# Power.net
KiCad netlist of a schematic drawn in Altium Designer
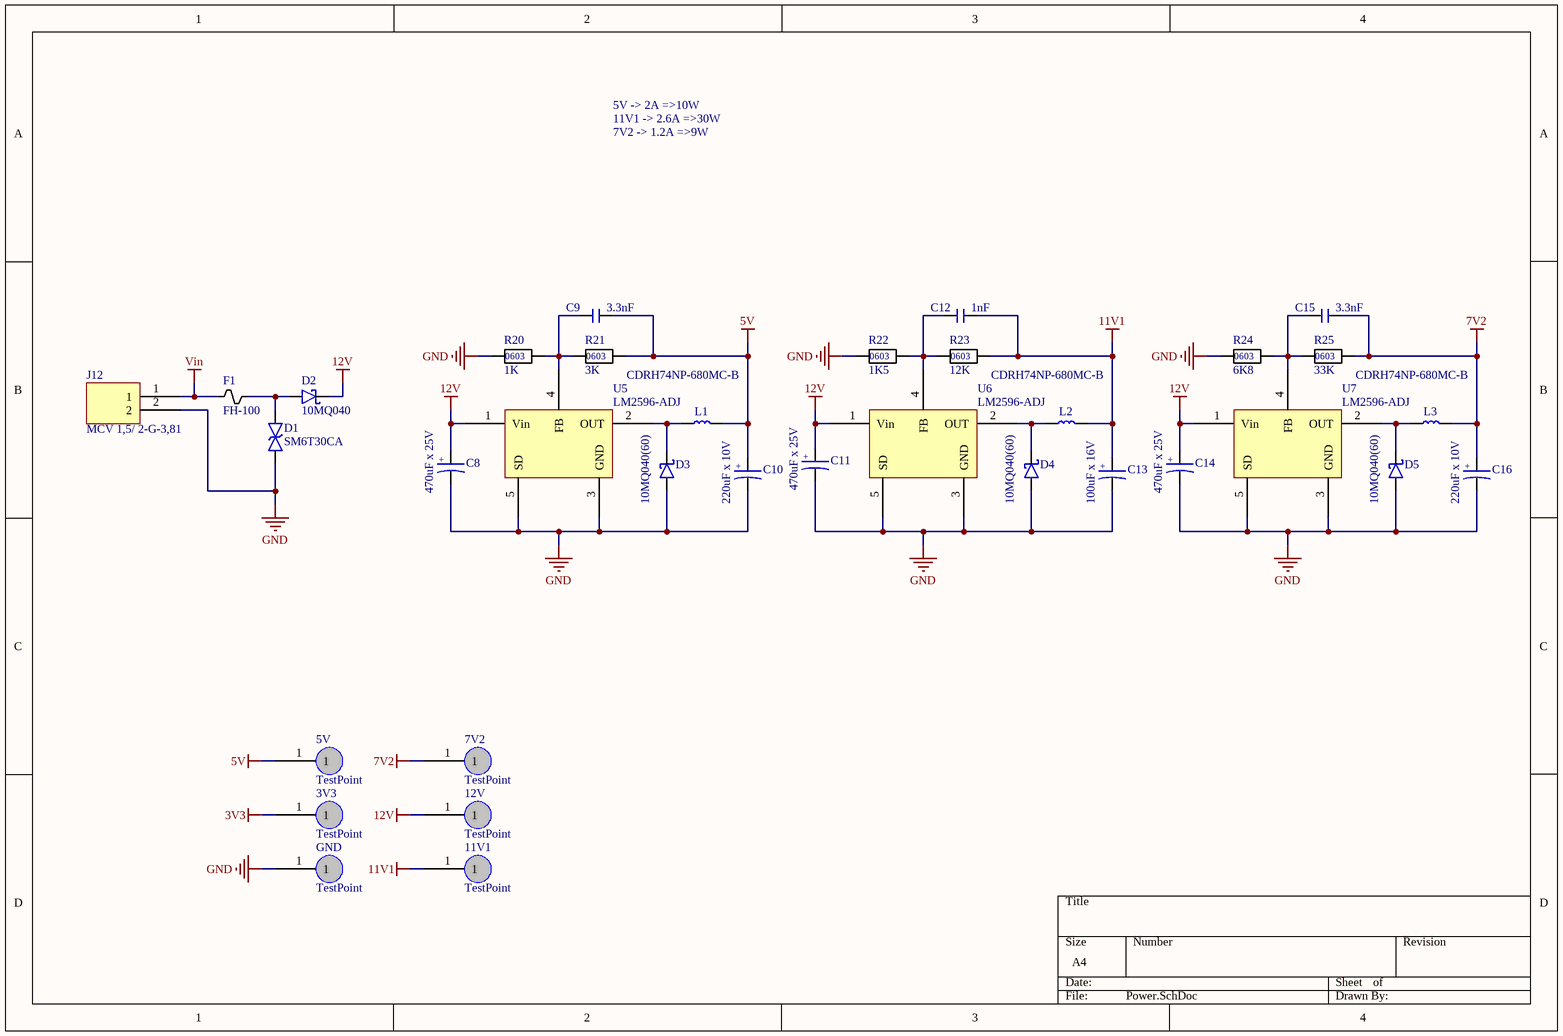
[diagram p0: Power.SchDoc]

(export (version "E")
  (design (tool "Eeschema 10.0.6"))
  (components
    (comp (ref "3V3")
      (value "TestPoint")
      (footprint "TestPoint")
      (libsource (lib "Popular") (part "TestPoint"))
    )
    (comp (ref "5V")
      (value "TestPoint")
      (footprint "TestPoint")
      (libsource (lib "Popular") (part "TestPoint"))
    )
    (comp (ref "7V2")
      (value "TestPoint")
      (footprint "TestPoint")
      (libsource (lib "Popular") (part "TestPoint"))
    )
    (comp (ref "11V1")
      (value "TestPoint")
      (footprint "TestPoint")
      (libsource (lib "Popular") (part "TestPoint"))
    )
    (comp (ref "12V")
      (value "TestPoint")
      (footprint "TestPoint")
      (libsource (lib "Popular") (part "TestPoint"))
    )
    (comp (ref "C8")
      (value "470uF x 25V")
      (footprint "ALCAP_8x16")
      (libsource (lib "Popular") (part "Electrolit"))
    )
    (comp (ref "C9") (value "3.3nF") (footprint "CHIP_C_0603") (libsource (lib "Popular") (part "CHIP_C")))
    (comp (ref "C10")
      (value "220uF x 10V")
      (footprint "Tantal - D")
      (libsource (lib "Popular") (part "Tantal"))
    )
    (comp (ref "C11")
      (value "470uF x 25V")
      (footprint "ALCAP_8x16")
      (libsource (lib "Popular") (part "Electrolit"))
    )
    (comp (ref "C12") (value "1nF") (footprint "CHIP_C_0603") (libsource (lib "Popular") (part "CHIP_C")))
    (comp (ref "C13")
      (value "100uF x 16V")
      (footprint "Tantal - B")
      (libsource (lib "Popular") (part "Tantal"))
    )
    (comp (ref "C14")
      (value "470uF x 25V")
      (footprint "ALCAP_8x16")
      (libsource (lib "Popular") (part "Electrolit"))
    )
    (comp (ref "C15") (value "3.3nF") (footprint "CHIP_C_0603") (libsource (lib "Popular") (part "CHIP_C")))
    (comp (ref "C16")
      (value "220uF x 10V")
      (footprint "Tantal - D")
      (libsource (lib "Popular") (part "Tantal"))
    )
    (comp (ref "D1")
      (value "SM6T30CA")
      (footprint "DO-214AA")
      (description "ESD protection")
      (libsource (lib "Popular") (part "SM6T27CA"))
    )
    (comp (ref "D2")
      (value "10MQ040")
      (footprint "DO214-AC")
      (description "Rectifier diode")
      (libsource (lib "Popular") (part "10MQ040"))
    )
    (comp (ref "D3")
      (value "10MQ040(60)")
      (footprint "DO214-AC")
      (description "Rectifier diode")
      (libsource (lib "Popular") (part "10MQ040"))
    )
    (comp (ref "D4")
      (value "10MQ040(60)")
      (footprint "DO214-AC")
      (description "Rectifier diode")
      (libsource (lib "Popular") (part "10MQ040"))
    )
    (comp (ref "D5")
      (value "10MQ040(60)")
      (footprint "DO214-AC")
      (description "Rectifier diode")
      (libsource (lib "Popular") (part "10MQ040"))
    )
    (comp (ref "F1")
      (value "FH-100")
      (footprint "FH-100")
      (libsource (lib "Popular") (part "FuseGlass 5x20"))
    )
    (comp (ref "GND")
      (value "TestPoint")
      (footprint "TestPoint")
      (libsource (lib "Popular") (part "TestPoint"))
    )
    (comp (ref "J12")
      (value "MCV 1,5/ 2-G-3,81")
      (footprint "CON_2_5.08")
      (libsource (lib "Popular") (part "MCV 1,5/ 2-G-3,81"))
    )
    (comp (ref "L1")
      (value "CDRH74NP-680MC-B")
      (footprint "CDRH74")
      (libsource (lib "Popular") (part "CDRH74"))
    )
    (comp (ref "L2")
      (value "CDRH74NP-680MC-B")
      (footprint "CDRH74")
      (libsource (lib "Popular") (part "CDRH74"))
    )
    (comp (ref "L3")
      (value "CDRH74NP-680MC-B")
      (footprint "CDRH74")
      (libsource (lib "Popular") (part "CDRH74"))
    )
    (comp (ref "R20") (value "1K") (footprint "CHIP_R_0603") (libsource (lib "Popular") (part "RES_0603")))
    (comp (ref "R21") (value "3K") (footprint "CHIP_R_0603") (libsource (lib "Popular") (part "RES_0603")))
    (comp (ref "R22") (value "1K5") (footprint "CHIP_R_0603") (libsource (lib "Popular") (part "RES_0603")))
    (comp (ref "R23") (value "12K") (footprint "CHIP_R_0603") (libsource (lib "Popular") (part "RES_0603")))
    (comp (ref "R24") (value "6K8") (footprint "CHIP_R_0603") (libsource (lib "Popular") (part "RES_0603")))
    (comp (ref "R25") (value "33K") (footprint "CHIP_R_0603") (libsource (lib "Popular") (part "RES_0603")))
    (comp (ref "U5")
      (value "LM2596-ADJ")
      (footprint "TO-220-5")
      (libsource (lib "Popular") (part "LM2596 (5 pin)"))
    )
    (comp (ref "U6")
      (value "LM2596-ADJ")
      (footprint "TO-220-5")
      (libsource (lib "Popular") (part "LM2596 (5 pin)"))
    )
    (comp (ref "U7")
      (value "LM2596-ADJ")
      (footprint "TO-220-5")
      (libsource (lib "Popular") (part "LM2596 (5 pin)"))
    )
  )
  (nets
    (net (code "1") (name "3V3") (class "Default")
      (node (ref "3V3") (pin "1") (pinfunction "1_1") (pintype "passive"))
    )
    (net (code "2") (name "5V") (class "Default")
      (node (ref "5V") (pin "1") (pinfunction "1_1") (pintype "passive"))
      (node (ref "C10") (pin "1") (pinfunction "1_1") (pintype "passive"))
      (node (ref "C9") (pin "1") (pinfunction "1_1") (pintype "passive"))
      (node (ref "L1") (pin "2") (pinfunction "2_2") (pintype "passive"))
      (node (ref "R21") (pin "2") (pinfunction "2_2") (pintype "passive"))
    )
    (net (code "3") (name "7V2") (class "Default")
      (node (ref "7V2") (pin "1") (pinfunction "1_1") (pintype "passive"))
      (node (ref "C15") (pin "1") (pinfunction "1_1") (pintype "passive"))
      (node (ref "C16") (pin "1") (pinfunction "1_1") (pintype "passive"))
      (node (ref "L3") (pin "2") (pinfunction "2_2") (pintype "passive"))
      (node (ref "R25") (pin "2") (pinfunction "2_2") (pintype "passive"))
    )
    (net (code "4") (name "11V1") (class "Default")
      (node (ref "11V1") (pin "1") (pinfunction "1_1") (pintype "passive"))
      (node (ref "C12") (pin "1") (pinfunction "1_1") (pintype "passive"))
      (node (ref "C13") (pin "1") (pinfunction "1_1") (pintype "passive"))
      (node (ref "L2") (pin "2") (pinfunction "2_2") (pintype "passive"))
      (node (ref "R23") (pin "2") (pinfunction "2_2") (pintype "passive"))
    )
    (net (code "5") (name "12V") (class "Default")
      (node (ref "12V") (pin "1") (pinfunction "1_1") (pintype "passive"))
      (node (ref "C11") (pin "1") (pinfunction "1_1") (pintype "passive"))
      (node (ref "C14") (pin "1") (pinfunction "1_1") (pintype "passive"))
      (node (ref "C8") (pin "1") (pinfunction "1_1") (pintype "passive"))
      (node (ref "D2") (pin "2") (pinfunction "2_2") (pintype "passive"))
      (node (ref "U5") (pin "1") (pinfunction "Vin_1") (pintype "passive"))
      (node (ref "U6") (pin "1") (pinfunction "Vin_1") (pintype "passive"))
      (node (ref "U7") (pin "1") (pinfunction "Vin_1") (pintype "passive"))
    )
    (net (code "6") (name "GND") (class "Default")
      (node (ref "C10") (pin "2") (pinfunction "2_2") (pintype "passive"))
      (node (ref "C11") (pin "2") (pinfunction "2_2") (pintype "passive"))
      (node (ref "C13") (pin "2") (pinfunction "2_2") (pintype "passive"))
      (node (ref "C14") (pin "2") (pinfunction "2_2") (pintype "passive"))
      (node (ref "C16") (pin "2") (pinfunction "2_2") (pintype "passive"))
      (node (ref "C8") (pin "2") (pinfunction "2_2") (pintype "passive"))
      (node (ref "D1") (pin "2") (pinfunction "2_2") (pintype "passive"))
      (node (ref "D3") (pin "1") (pinfunction "1_1") (pintype "passive"))
      (node (ref "D4") (pin "1") (pinfunction "1_1") (pintype "passive"))
      (node (ref "D5") (pin "1") (pinfunction "1_1") (pintype "passive"))
      (node (ref "GND") (pin "1") (pinfunction "1_1") (pintype "passive"))
      (node (ref "J12") (pin "2") (pinfunction "2_2") (pintype "passive"))
      (node (ref "R20") (pin "1") (pinfunction "1_1") (pintype "passive"))
      (node (ref "R22") (pin "1") (pinfunction "1_1") (pintype "passive"))
      (node (ref "R24") (pin "1") (pinfunction "1_1") (pintype "passive"))
      (node (ref "U5") (pin "3") (pinfunction "GND_3") (pintype "passive"))
      (node (ref "U5") (pin "5") (pinfunction "SD_5") (pintype "passive"))
      (node (ref "U6") (pin "3") (pinfunction "GND_3") (pintype "passive"))
      (node (ref "U6") (pin "5") (pinfunction "SD_5") (pintype "passive"))
      (node (ref "U7") (pin "3") (pinfunction "GND_3") (pintype "passive"))
      (node (ref "U7") (pin "5") (pinfunction "SD_5") (pintype "passive"))
    )
    (net (code "7") (name "Net-(D1-Pad1)") (class "Default")
      (node (ref "D1") (pin "1") (pinfunction "1_1") (pintype "passive"))
      (node (ref "D2") (pin "1") (pinfunction "1_1") (pintype "passive"))
      (node (ref "F1") (pin "2") (pinfunction "2_2") (pintype "passive"))
    )
    (net (code "8") (name "Net-(U5-FB)") (class "Default")
      (node (ref "C9") (pin "2") (pinfunction "2_2") (pintype "passive"))
      (node (ref "R20") (pin "2") (pinfunction "2_2") (pintype "passive"))
      (node (ref "R21") (pin "1") (pinfunction "1_1") (pintype "passive"))
      (node (ref "U5") (pin "4") (pinfunction "FB_4") (pintype "passive"))
    )
    (net (code "9") (name "Net-(U5-OUT)") (class "Default")
      (node (ref "D3") (pin "2") (pinfunction "2_2") (pintype "passive"))
      (node (ref "L1") (pin "1") (pinfunction "1_1") (pintype "passive"))
      (node (ref "U5") (pin "2") (pinfunction "OUT_2") (pintype "passive"))
    )
    (net (code "10") (name "Net-(U6-FB)") (class "Default")
      (node (ref "C12") (pin "2") (pinfunction "2_2") (pintype "passive"))
      (node (ref "R22") (pin "2") (pinfunction "2_2") (pintype "passive"))
      (node (ref "R23") (pin "1") (pinfunction "1_1") (pintype "passive"))
      (node (ref "U6") (pin "4") (pinfunction "FB_4") (pintype "passive"))
    )
    (net (code "11") (name "Net-(U6-OUT)") (class "Default")
      (node (ref "D4") (pin "2") (pinfunction "2_2") (pintype "passive"))
      (node (ref "L2") (pin "1") (pinfunction "1_1") (pintype "passive"))
      (node (ref "U6") (pin "2") (pinfunction "OUT_2") (pintype "passive"))
    )
    (net (code "12") (name "Net-(U7-FB)") (class "Default")
      (node (ref "C15") (pin "2") (pinfunction "2_2") (pintype "passive"))
      (node (ref "R24") (pin "2") (pinfunction "2_2") (pintype "passive"))
      (node (ref "R25") (pin "1") (pinfunction "1_1") (pintype "passive"))
      (node (ref "U7") (pin "4") (pinfunction "FB_4") (pintype "passive"))
    )
    (net (code "13") (name "Net-(U7-OUT)") (class "Default")
      (node (ref "D5") (pin "2") (pinfunction "2_2") (pintype "passive"))
      (node (ref "L3") (pin "1") (pinfunction "1_1") (pintype "passive"))
      (node (ref "U7") (pin "2") (pinfunction "OUT_2") (pintype "passive"))
    )
    (net (code "14") (name "Vin") (class "Default")
      (node (ref "F1") (pin "1") (pinfunction "1_1") (pintype "passive"))
      (node (ref "J12") (pin "1") (pinfunction "1_1") (pintype "passive"))
    )
  )
)
